# IC.net
KiCad netlist of a schematic drawn in Altium Designer
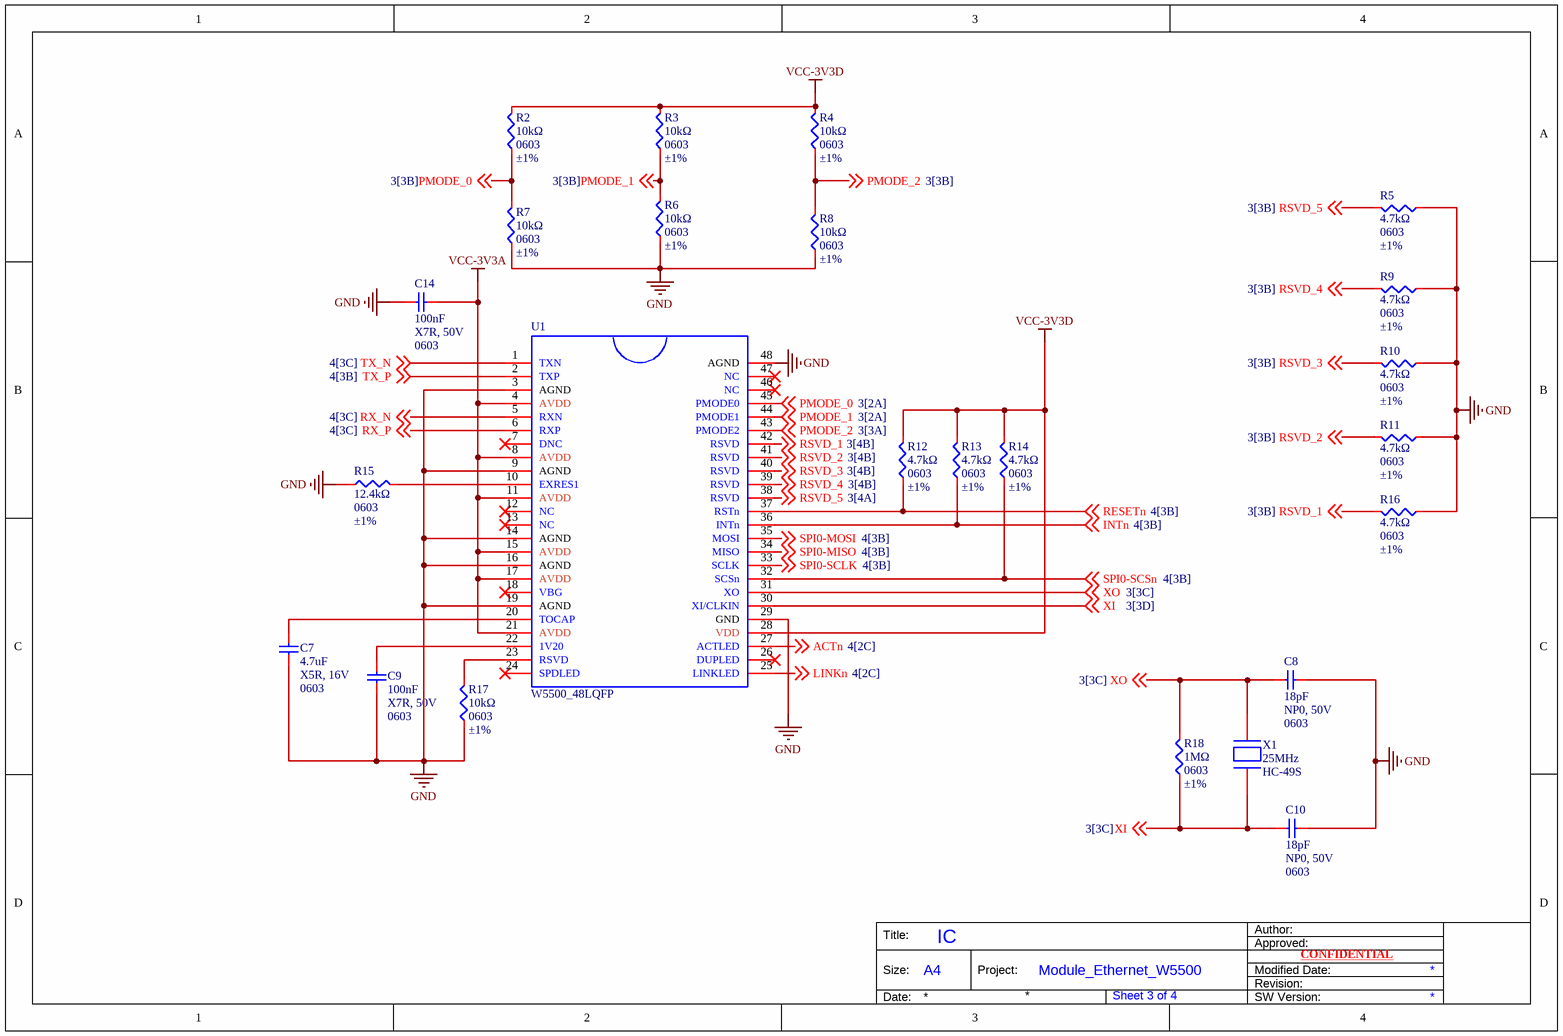
[diagram p0: IC.SchDoc]

(export (version "E")
  (design (tool "Eeschema 10.0.6"))
  (components
    (comp (ref "C7")
      (value "4.7uF")
      (footprint "C0603")
      (description "4.7uF ±10% 16V Ceramic Capacitor X5R 0603")
      (fields
        (field (name "MANUFACTURER") "Samsung Electro-Mechanics")
        (field (name "MFR. PART") "CL10A475KO8NNNC")
        (field (name "TEMPERATURE COEFFICIENT") "X5R, 16V")
        (field (name "PACKAGE") "0603")
      )
      (libsource (lib "Capacitor") (part "C0603_MLCC_4.7uF_X5R_16V"))
    )
    (comp (ref "C8")
      (value "18pF")
      (footprint "C0603")
      (description "18pF ±5% 50V Ceramic Capacitor NP0 0603")
      (fields
        (field (name "MANUFACTURER") "YAGEO")
        (field (name "MFR. PART") "CC0603JRNPO9BN180")
        (field (name "TEMPERATURE COEFFICIENT") "NP0, 50V")
        (field (name "PACKAGE") "0603")
      )
      (libsource (lib "Capacitor") (part "C0603_MLCC_18pF_NP0_50V"))
    )
    (comp (ref "C9")
      (value "100nF")
      (footprint "C0603")
      (description "50V 100nF X7R ±10% 0603 Multilayer Ceramic Capacitors MLCC - SMD/SMT ROHS")
      (fields
        (field (name "MANUFACTURER") "YAGEO")
        (field (name "MFR. PART") "CC0603KRX7R9BB104")
        (field (name "TEMPERATURE COEFFICIENT") "X7R, 50V")
        (field (name "PACKAGE") "0603")
      )
      (libsource (lib "Capacitor") (part "C0603_MLCC_100nF_X7R_50V"))
    )
    (comp (ref "C10")
      (value "18pF")
      (footprint "C0603")
      (description "18pF ±5% 50V Ceramic Capacitor NP0 0603")
      (fields
        (field (name "MANUFACTURER") "YAGEO")
        (field (name "MFR. PART") "CC0603JRNPO9BN180")
        (field (name "TEMPERATURE COEFFICIENT") "NP0, 50V")
        (field (name "PACKAGE") "0603")
      )
      (libsource (lib "Capacitor") (part "C0603_MLCC_18pF_NP0_50V"))
    )
    (comp (ref "C14")
      (value "100nF")
      (footprint "C0603")
      (description "50V 100nF X7R ±10% 0603 Multilayer Ceramic Capacitors MLCC - SMD/SMT ROHS")
      (fields
        (field (name "MANUFACTURER") "YAGEO")
        (field (name "MFR. PART") "CC0603KRX7R9BB104")
        (field (name "TEMPERATURE COEFFICIENT") "X7R, 50V")
        (field (name "PACKAGE") "0603")
      )
      (libsource (lib "Capacitor") (part "C0603_MLCC_100nF_X7R_50V"))
    )
    (comp (ref "R2")
      (value "10kΩ")
      (footprint "R0603")
      (description "100mW Thick Film Resistor 75V ±100ppm/℃ ±1% 10kΩ 0603 Chip Resistor - Surface Mount ROHS")
      (fields
        (field (name "MANUFACTURER") "YAGEO")
        (field (name "MFR. PART") "RC0603FR-0710KL")
        (field (name "PACKAGE") "0603")
        (field (name "TOLERANCE") "±1%")
      )
      (libsource (lib "Resistor") (part "R0603_10kΩ_±1%"))
    )
    (comp (ref "R3")
      (value "10kΩ")
      (footprint "R0603")
      (description "100mW Thick Film Resistor 75V ±100ppm/℃ ±1% 10kΩ 0603 Chip Resistor - Surface Mount ROHS")
      (fields
        (field (name "MANUFACTURER") "YAGEO")
        (field (name "MFR. PART") "RC0603FR-0710KL")
        (field (name "PACKAGE") "0603")
        (field (name "TOLERANCE") "±1%")
      )
      (libsource (lib "Resistor") (part "R0603_10kΩ_±1%"))
    )
    (comp (ref "R4")
      (value "10kΩ")
      (footprint "R0603")
      (description "100mW Thick Film Resistor 75V ±100ppm/℃ ±1% 10kΩ 0603 Chip Resistor - Surface Mount ROHS")
      (fields
        (field (name "MANUFACTURER") "YAGEO")
        (field (name "MFR. PART") "RC0603FR-0710KL")
        (field (name "PACKAGE") "0603")
        (field (name "TOLERANCE") "±1%")
      )
      (libsource (lib "Resistor") (part "R0603_10kΩ_±1%"))
    )
    (comp (ref "R5")
      (value "4.7kΩ")
      (footprint "R0603")
      (description "100mW Thick Film Resistor 75V ±100ppm/℃ ±1% 4.7kΩ 0603 Chip Resistor - Surface Mount ROHS")
      (fields
        (field (name "MANUFACTURER") "YAGEO")
        (field (name "MFR. PART") "RC0603FR-074K7L")
        (field (name "PACKAGE") "0603")
        (field (name "TOLERANCE") "±1%")
      )
      (libsource (lib "Resistor") (part "R0603_4.7kΩ_±1%"))
    )
    (comp (ref "R6")
      (value "10kΩ")
      (footprint "R0603")
      (description "100mW Thick Film Resistor 75V ±100ppm/℃ ±1% 10kΩ 0603 Chip Resistor - Surface Mount ROHS")
      (fields
        (field (name "MANUFACTURER") "YAGEO")
        (field (name "MFR. PART") "RC0603FR-0710KL")
        (field (name "PACKAGE") "0603")
        (field (name "TOLERANCE") "±1%")
      )
      (libsource (lib "Resistor") (part "R0603_10kΩ_±1%"))
    )
    (comp (ref "R7")
      (value "10kΩ")
      (footprint "R0603")
      (description "100mW Thick Film Resistor 75V ±100ppm/℃ ±1% 10kΩ 0603 Chip Resistor - Surface Mount ROHS")
      (fields
        (field (name "MANUFACTURER") "YAGEO")
        (field (name "MFR. PART") "RC0603FR-0710KL")
        (field (name "PACKAGE") "0603")
        (field (name "TOLERANCE") "±1%")
      )
      (libsource (lib "Resistor") (part "R0603_10kΩ_±1%"))
    )
    (comp (ref "R8")
      (value "10kΩ")
      (footprint "R0603")
      (description "100mW Thick Film Resistor 75V ±100ppm/℃ ±1% 10kΩ 0603 Chip Resistor - Surface Mount ROHS")
      (fields
        (field (name "MANUFACTURER") "YAGEO")
        (field (name "MFR. PART") "RC0603FR-0710KL")
        (field (name "PACKAGE") "0603")
        (field (name "TOLERANCE") "±1%")
      )
      (libsource (lib "Resistor") (part "R0603_10kΩ_±1%"))
    )
    (comp (ref "R9")
      (value "4.7kΩ")
      (footprint "R0603")
      (description "100mW Thick Film Resistor 75V ±100ppm/℃ ±1% 4.7kΩ 0603 Chip Resistor - Surface Mount ROHS")
      (fields
        (field (name "MANUFACTURER") "YAGEO")
        (field (name "MFR. PART") "RC0603FR-074K7L")
        (field (name "PACKAGE") "0603")
        (field (name "TOLERANCE") "±1%")
      )
      (libsource (lib "Resistor") (part "R0603_4.7kΩ_±1%"))
    )
    (comp (ref "R10")
      (value "4.7kΩ")
      (footprint "R0603")
      (description "100mW Thick Film Resistor 75V ±100ppm/℃ ±1% 4.7kΩ 0603 Chip Resistor - Surface Mount ROHS")
      (fields
        (field (name "MANUFACTURER") "YAGEO")
        (field (name "MFR. PART") "RC0603FR-074K7L")
        (field (name "PACKAGE") "0603")
        (field (name "TOLERANCE") "±1%")
      )
      (libsource (lib "Resistor") (part "R0603_4.7kΩ_±1%"))
    )
    (comp (ref "R11")
      (value "4.7kΩ")
      (footprint "R0603")
      (description "100mW Thick Film Resistor 75V ±100ppm/℃ ±1% 4.7kΩ 0603 Chip Resistor - Surface Mount ROHS")
      (fields
        (field (name "MANUFACTURER") "YAGEO")
        (field (name "MFR. PART") "RC0603FR-074K7L")
        (field (name "PACKAGE") "0603")
        (field (name "TOLERANCE") "±1%")
      )
      (libsource (lib "Resistor") (part "R0603_4.7kΩ_±1%"))
    )
    (comp (ref "R12")
      (value "4.7kΩ")
      (footprint "R0603")
      (description "100mW Thick Film Resistor 75V ±100ppm/℃ ±1% 4.7kΩ 0603 Chip Resistor - Surface Mount ROHS")
      (fields
        (field (name "MANUFACTURER") "YAGEO")
        (field (name "MFR. PART") "RC0603FR-074K7L")
        (field (name "PACKAGE") "0603")
        (field (name "TOLERANCE") "±1%")
      )
      (libsource (lib "Resistor") (part "R0603_4.7kΩ_±1%"))
    )
    (comp (ref "R13")
      (value "4.7kΩ")
      (footprint "R0603")
      (description "100mW Thick Film Resistor 75V ±100ppm/℃ ±1% 4.7kΩ 0603 Chip Resistor - Surface Mount ROHS")
      (fields
        (field (name "MANUFACTURER") "YAGEO")
        (field (name "MFR. PART") "RC0603FR-074K7L")
        (field (name "PACKAGE") "0603")
        (field (name "TOLERANCE") "±1%")
      )
      (libsource (lib "Resistor") (part "R0603_4.7kΩ_±1%"))
    )
    (comp (ref "R14")
      (value "4.7kΩ")
      (footprint "R0603")
      (description "100mW Thick Film Resistor 75V ±100ppm/℃ ±1% 4.7kΩ 0603 Chip Resistor - Surface Mount ROHS")
      (fields
        (field (name "MANUFACTURER") "YAGEO")
        (field (name "MFR. PART") "RC0603FR-074K7L")
        (field (name "PACKAGE") "0603")
        (field (name "TOLERANCE") "±1%")
      )
      (libsource (lib "Resistor") (part "R0603_4.7kΩ_±1%"))
    )
    (comp (ref "R15")
      (value "12.4kΩ")
      (footprint "R0603")
      (description "100mW 12.4kΩ 75V Thick Film Resistor ±100ppm/℃ ±1% 0603 Chip Resistor - Surface Mount RoHS")
      (fields
        (field (name "MANUFACTURER") "YAGEO")
        (field (name "MFR. PART") "RC0603FR-0712K4L")
        (field (name "PACKAGE") "0603")
        (field (name "TOLERANCE") "±1%")
      )
      (libsource (lib "Resistor") (part "R0603_12.4kΩ_±1%"))
    )
    (comp (ref "R16")
      (value "4.7kΩ")
      (footprint "R0603")
      (description "100mW Thick Film Resistor 75V ±100ppm/℃ ±1% 4.7kΩ 0603 Chip Resistor - Surface Mount ROHS")
      (fields
        (field (name "MANUFACTURER") "YAGEO")
        (field (name "MFR. PART") "RC0603FR-074K7L")
        (field (name "PACKAGE") "0603")
        (field (name "TOLERANCE") "±1%")
      )
      (libsource (lib "Resistor") (part "R0603_4.7kΩ_±1%"))
    )
    (comp (ref "R17")
      (value "10kΩ")
      (footprint "R0603")
      (description "100mW Thick Film Resistor 75V ±100ppm/℃ ±1% 10kΩ 0603 Chip Resistor - Surface Mount ROHS")
      (fields
        (field (name "MANUFACTURER") "YAGEO")
        (field (name "MFR. PART") "RC0603FR-0710KL")
        (field (name "PACKAGE") "0603")
        (field (name "TOLERANCE") "±1%")
      )
      (libsource (lib "Resistor") (part "R0603_10kΩ_±1%"))
    )
    (comp (ref "R18")
      (value "1MΩ")
      (footprint "R0603")
      (description "100mW Thick Film Resistor 75V ±100ppm/℃ ±1% 1MΩ 0603 Chip Resistor - Surface Mount ROHS")
      (fields
        (field (name "MANUFACTURER") "YAGEO")
        (field (name "MFR. PART") "RC0603FR-071ML")
        (field (name "PACKAGE") "0603")
        (field (name "TOLERANCE") "±1%")
      )
      (libsource (lib "Resistor") (part "R0603_1MΩ_±1%"))
    )
    (comp (ref "U1")
      (value "W5500_48LQFP")
      (footprint "48LQFP (7*7)")
      (description "LQFP-48(7x7) Interface Controllers RoHS")
      (fields (field (name "MANUFACTURER") "WIZNETTHE TICKET") (field (name "MFR. PART") "TPS61175PWPR"))
      (libsource (lib "IC") (part "W5500_48LQFP"))
    )
    (comp (ref "X1")
      (value "25MHz")
      (footprint "HC-49S")
      (description "Crystal 25MHz ±20ppm 20pF HC-49S")
      (fields
        (field (name "MANUFACTURER") "YXC Crystal Oscillators")
        (field (name "MFR. PART") "X49SD25MSD2SC")
        (field (name "PACKAGE") "HC-49S")
      )
      (libsource (lib "CRYSTAL") (part "Crystal_25Mhz_HC49S"))
    )
  )
  (nets
    (net (code "1") (name "ACTn") (class "Default")
      (node (ref "U1") (pin "27") (pinfunction "ACTLED_27") (pintype "passive"))
    )
    (net (code "2") (name "GND") (class "Default")
      (node (ref "C10") (pin "2") (pinfunction "2_2") (pintype "passive"))
      (node (ref "C14") (pin "2") (pinfunction "2_2") (pintype "passive"))
      (node (ref "C7") (pin "1") (pinfunction "1_1") (pintype "passive"))
      (node (ref "C8") (pin "2") (pinfunction "2_2") (pintype "passive"))
      (node (ref "C9") (pin "1") (pinfunction "1_1") (pintype "passive"))
      (node (ref "R10") (pin "1") (pinfunction "1_1") (pintype "passive"))
      (node (ref "R11") (pin "1") (pinfunction "1_1") (pintype "passive"))
      (node (ref "R15") (pin "1") (pinfunction "1_1") (pintype "passive"))
      (node (ref "R16") (pin "1") (pinfunction "1_1") (pintype "passive"))
      (node (ref "R17") (pin "1") (pinfunction "1_1") (pintype "passive"))
      (node (ref "R5") (pin "1") (pinfunction "1_1") (pintype "passive"))
      (node (ref "R6") (pin "1") (pinfunction "1_1") (pintype "passive"))
      (node (ref "R7") (pin "1") (pinfunction "1_1") (pintype "passive"))
      (node (ref "R8") (pin "1") (pinfunction "1_1") (pintype "passive"))
      (node (ref "R9") (pin "1") (pinfunction "1_1") (pintype "passive"))
      (node (ref "U1") (pin "14") (pinfunction "AGND_14") (pintype "passive"))
      (node (ref "U1") (pin "16") (pinfunction "AGND_16") (pintype "passive"))
      (node (ref "U1") (pin "19") (pinfunction "AGND_19") (pintype "passive"))
      (node (ref "U1") (pin "29") (pinfunction "GND_29") (pintype "passive"))
      (node (ref "U1") (pin "3") (pinfunction "AGND_3") (pintype "passive"))
      (node (ref "U1") (pin "48") (pinfunction "AGND_48") (pintype "passive"))
      (node (ref "U1") (pin "9") (pinfunction "AGND_9") (pintype "passive"))
    )
    (net (code "3") (name "INTn") (class "Default")
      (node (ref "R13") (pin "1") (pinfunction "1_1") (pintype "passive"))
      (node (ref "U1") (pin "36") (pinfunction "INTn_36") (pintype "passive"))
    )
    (net (code "4") (name "LINKn") (class "Default")
      (node (ref "U1") (pin "25") (pinfunction "LINKLED_25") (pintype "passive"))
    )
    (net (code "5") (name "Net-(R17-Pad2)") (class "Default")
      (node (ref "R17") (pin "2") (pinfunction "2_2") (pintype "passive"))
      (node (ref "U1") (pin "23") (pinfunction "RSVD_23") (pintype "passive"))
    )
    (net (code "6") (name "Net-(U1-1V20)") (class "Default")
      (node (ref "C9") (pin "2") (pinfunction "2_2") (pintype "passive"))
      (node (ref "U1") (pin "22") (pinfunction "1V20_22") (pintype "passive"))
    )
    (net (code "7") (name "Net-(U1-EXRES1)") (class "Default")
      (node (ref "R15") (pin "2") (pinfunction "2_2") (pintype "passive"))
      (node (ref "U1") (pin "10") (pinfunction "EXRES1_10") (pintype "passive"))
    )
    (net (code "8") (name "Net-(U1-TOCAP)") (class "Default")
      (node (ref "C7") (pin "2") (pinfunction "2_2") (pintype "passive"))
      (node (ref "U1") (pin "20") (pinfunction "TOCAP_20") (pintype "passive"))
    )
    (net (code "9") (name "PMODE_0") (class "Default")
      (node (ref "R2") (pin "1") (pinfunction "1_1") (pintype "passive"))
      (node (ref "R7") (pin "2") (pinfunction "2_2") (pintype "passive"))
      (node (ref "U1") (pin "45") (pinfunction "PMODE0_45") (pintype "passive"))
    )
    (net (code "10") (name "PMODE_1") (class "Default")
      (node (ref "R3") (pin "1") (pinfunction "1_1") (pintype "passive"))
      (node (ref "R6") (pin "2") (pinfunction "2_2") (pintype "passive"))
      (node (ref "U1") (pin "44") (pinfunction "PMODE1_44") (pintype "passive"))
    )
    (net (code "11") (name "PMODE_2") (class "Default")
      (node (ref "R4") (pin "1") (pinfunction "1_1") (pintype "passive"))
      (node (ref "R8") (pin "2") (pinfunction "2_2") (pintype "passive"))
      (node (ref "U1") (pin "43") (pinfunction "PMODE2_43") (pintype "passive"))
    )
    (net (code "12") (name "RESETn") (class "Default")
      (node (ref "R12") (pin "1") (pinfunction "1_1") (pintype "passive"))
      (node (ref "U1") (pin "37") (pinfunction "RSTn_37") (pintype "passive"))
    )
    (net (code "13") (name "RSVD_1") (class "Default")
      (node (ref "R16") (pin "2") (pinfunction "2_2") (pintype "passive"))
      (node (ref "U1") (pin "42") (pinfunction "RSVD_42") (pintype "passive"))
    )
    (net (code "14") (name "RSVD_2") (class "Default")
      (node (ref "R11") (pin "2") (pinfunction "2_2") (pintype "passive"))
      (node (ref "U1") (pin "41") (pinfunction "RSVD_41") (pintype "passive"))
    )
    (net (code "15") (name "RSVD_3") (class "Default")
      (node (ref "R10") (pin "2") (pinfunction "2_2") (pintype "passive"))
      (node (ref "U1") (pin "40") (pinfunction "RSVD_40") (pintype "passive"))
    )
    (net (code "16") (name "RSVD_4") (class "Default")
      (node (ref "R9") (pin "2") (pinfunction "2_2") (pintype "passive"))
      (node (ref "U1") (pin "39") (pinfunction "RSVD_39") (pintype "passive"))
    )
    (net (code "17") (name "RSVD_5") (class "Default")
      (node (ref "R5") (pin "2") (pinfunction "2_2") (pintype "passive"))
      (node (ref "U1") (pin "38") (pinfunction "RSVD_38") (pintype "passive"))
    )
    (net (code "18") (name "RX_N") (class "Default")
      (node (ref "U1") (pin "5") (pinfunction "RXN_5") (pintype "passive"))
    )
    (net (code "19") (name "RX_P") (class "Default")
      (node (ref "U1") (pin "6") (pinfunction "RXP_6") (pintype "passive"))
    )
    (net (code "20") (name "SPI0-MISO") (class "Default")
      (node (ref "U1") (pin "34") (pinfunction "MISO_34") (pintype "passive"))
    )
    (net (code "21") (name "SPI0-MOSI") (class "Default")
      (node (ref "U1") (pin "35") (pinfunction "MOSI_35") (pintype "passive"))
    )
    (net (code "22") (name "SPI0-SCLK") (class "Default")
      (node (ref "U1") (pin "33") (pinfunction "SCLK_33") (pintype "passive"))
    )
    (net (code "23") (name "SPI0-SCSn") (class "Default")
      (node (ref "R14") (pin "1") (pinfunction "1_1") (pintype "passive"))
      (node (ref "U1") (pin "32") (pinfunction "SCSn_32") (pintype "passive"))
    )
    (net (code "24") (name "TX_N") (class "Default")
      (node (ref "U1") (pin "1") (pinfunction "TXN_1") (pintype "passive"))
    )
    (net (code "25") (name "TX_P") (class "Default")
      (node (ref "U1") (pin "2") (pinfunction "TXP_2") (pintype "passive"))
    )
    (net (code "26") (name "VCC-3V3A") (class "Default")
      (node (ref "C14") (pin "1") (pinfunction "1_1") (pintype "passive"))
      (node (ref "U1") (pin "11") (pinfunction "AVDD_11") (pintype "passive"))
      (node (ref "U1") (pin "15") (pinfunction "AVDD_15") (pintype "passive"))
      (node (ref "U1") (pin "17") (pinfunction "AVDD_17") (pintype "passive"))
      (node (ref "U1") (pin "21") (pinfunction "AVDD_21") (pintype "passive"))
      (node (ref "U1") (pin "4") (pinfunction "AVDD_4") (pintype "passive"))
      (node (ref "U1") (pin "8") (pinfunction "AVDD_8") (pintype "passive"))
    )
    (net (code "27") (name "VCC-3V3D") (class "Default")
      (node (ref "R12") (pin "2") (pinfunction "2_2") (pintype "passive"))
      (node (ref "R13") (pin "2") (pinfunction "2_2") (pintype "passive"))
      (node (ref "R14") (pin "2") (pinfunction "2_2") (pintype "passive"))
      (node (ref "R2") (pin "2") (pinfunction "2_2") (pintype "passive"))
      (node (ref "R3") (pin "2") (pinfunction "2_2") (pintype "passive"))
      (node (ref "R4") (pin "2") (pinfunction "2_2") (pintype "passive"))
      (node (ref "U1") (pin "28") (pinfunction "VDD_28") (pintype "passive"))
    )
    (net (code "28") (name "XI") (class "Default")
      (node (ref "C10") (pin "1") (pinfunction "1_1") (pintype "passive"))
      (node (ref "R18") (pin "1") (pinfunction "1_1") (pintype "passive"))
      (node (ref "U1") (pin "30") (pinfunction "XI/CLKIN_30") (pintype "passive"))
      (node (ref "X1") (pin "1") (pinfunction "1_1") (pintype "passive"))
    )
    (net (code "29") (name "XO") (class "Default")
      (node (ref "C8") (pin "1") (pinfunction "1_1") (pintype "passive"))
      (node (ref "R18") (pin "2") (pinfunction "2_2") (pintype "passive"))
      (node (ref "U1") (pin "31") (pinfunction "XO_31") (pintype "passive"))
      (node (ref "X1") (pin "2") (pinfunction "2_2") (pintype "passive"))
    )
    (net (code "30") (name "unconnected-(U1-DNC-Pad7)") (class "Default")
      (node (ref "U1") (pin "7") (pinfunction "DNC_7") (pintype "passive+no_connect"))
    )
    (net (code "31") (name "unconnected-(U1-DUPLED-Pad26)") (class "Default")
      (node (ref "U1") (pin "26") (pinfunction "DUPLED_26") (pintype "passive+no_connect"))
    )
    (net (code "32") (name "unconnected-(U1-NC-Pad12)") (class "Default")
      (node (ref "U1") (pin "12") (pinfunction "NC_12") (pintype "passive+no_connect"))
    )
    (net (code "33") (name "unconnected-(U1-NC-Pad13)") (class "Default")
      (node (ref "U1") (pin "13") (pinfunction "NC_13") (pintype "passive+no_connect"))
    )
    (net (code "34") (name "unconnected-(U1-NC-Pad46)") (class "Default")
      (node (ref "U1") (pin "46") (pinfunction "NC_46") (pintype "passive+no_connect"))
    )
    (net (code "35") (name "unconnected-(U1-NC-Pad47)") (class "Default")
      (node (ref "U1") (pin "47") (pinfunction "NC_47") (pintype "passive+no_connect"))
    )
    (net (code "36") (name "unconnected-(U1-SPDLED-Pad24)") (class "Default")
      (node (ref "U1") (pin "24") (pinfunction "SPDLED_24") (pintype "passive+no_connect"))
    )
    (net (code "37") (name "unconnected-(U1-VBG-Pad18)") (class "Default")
      (node (ref "U1") (pin "18") (pinfunction "VBG_18") (pintype "passive+no_connect"))
    )
  )
)
